# T06_preliminarySchematic_v3.net
KiCad netlist of a schematic drawn in EAGLE
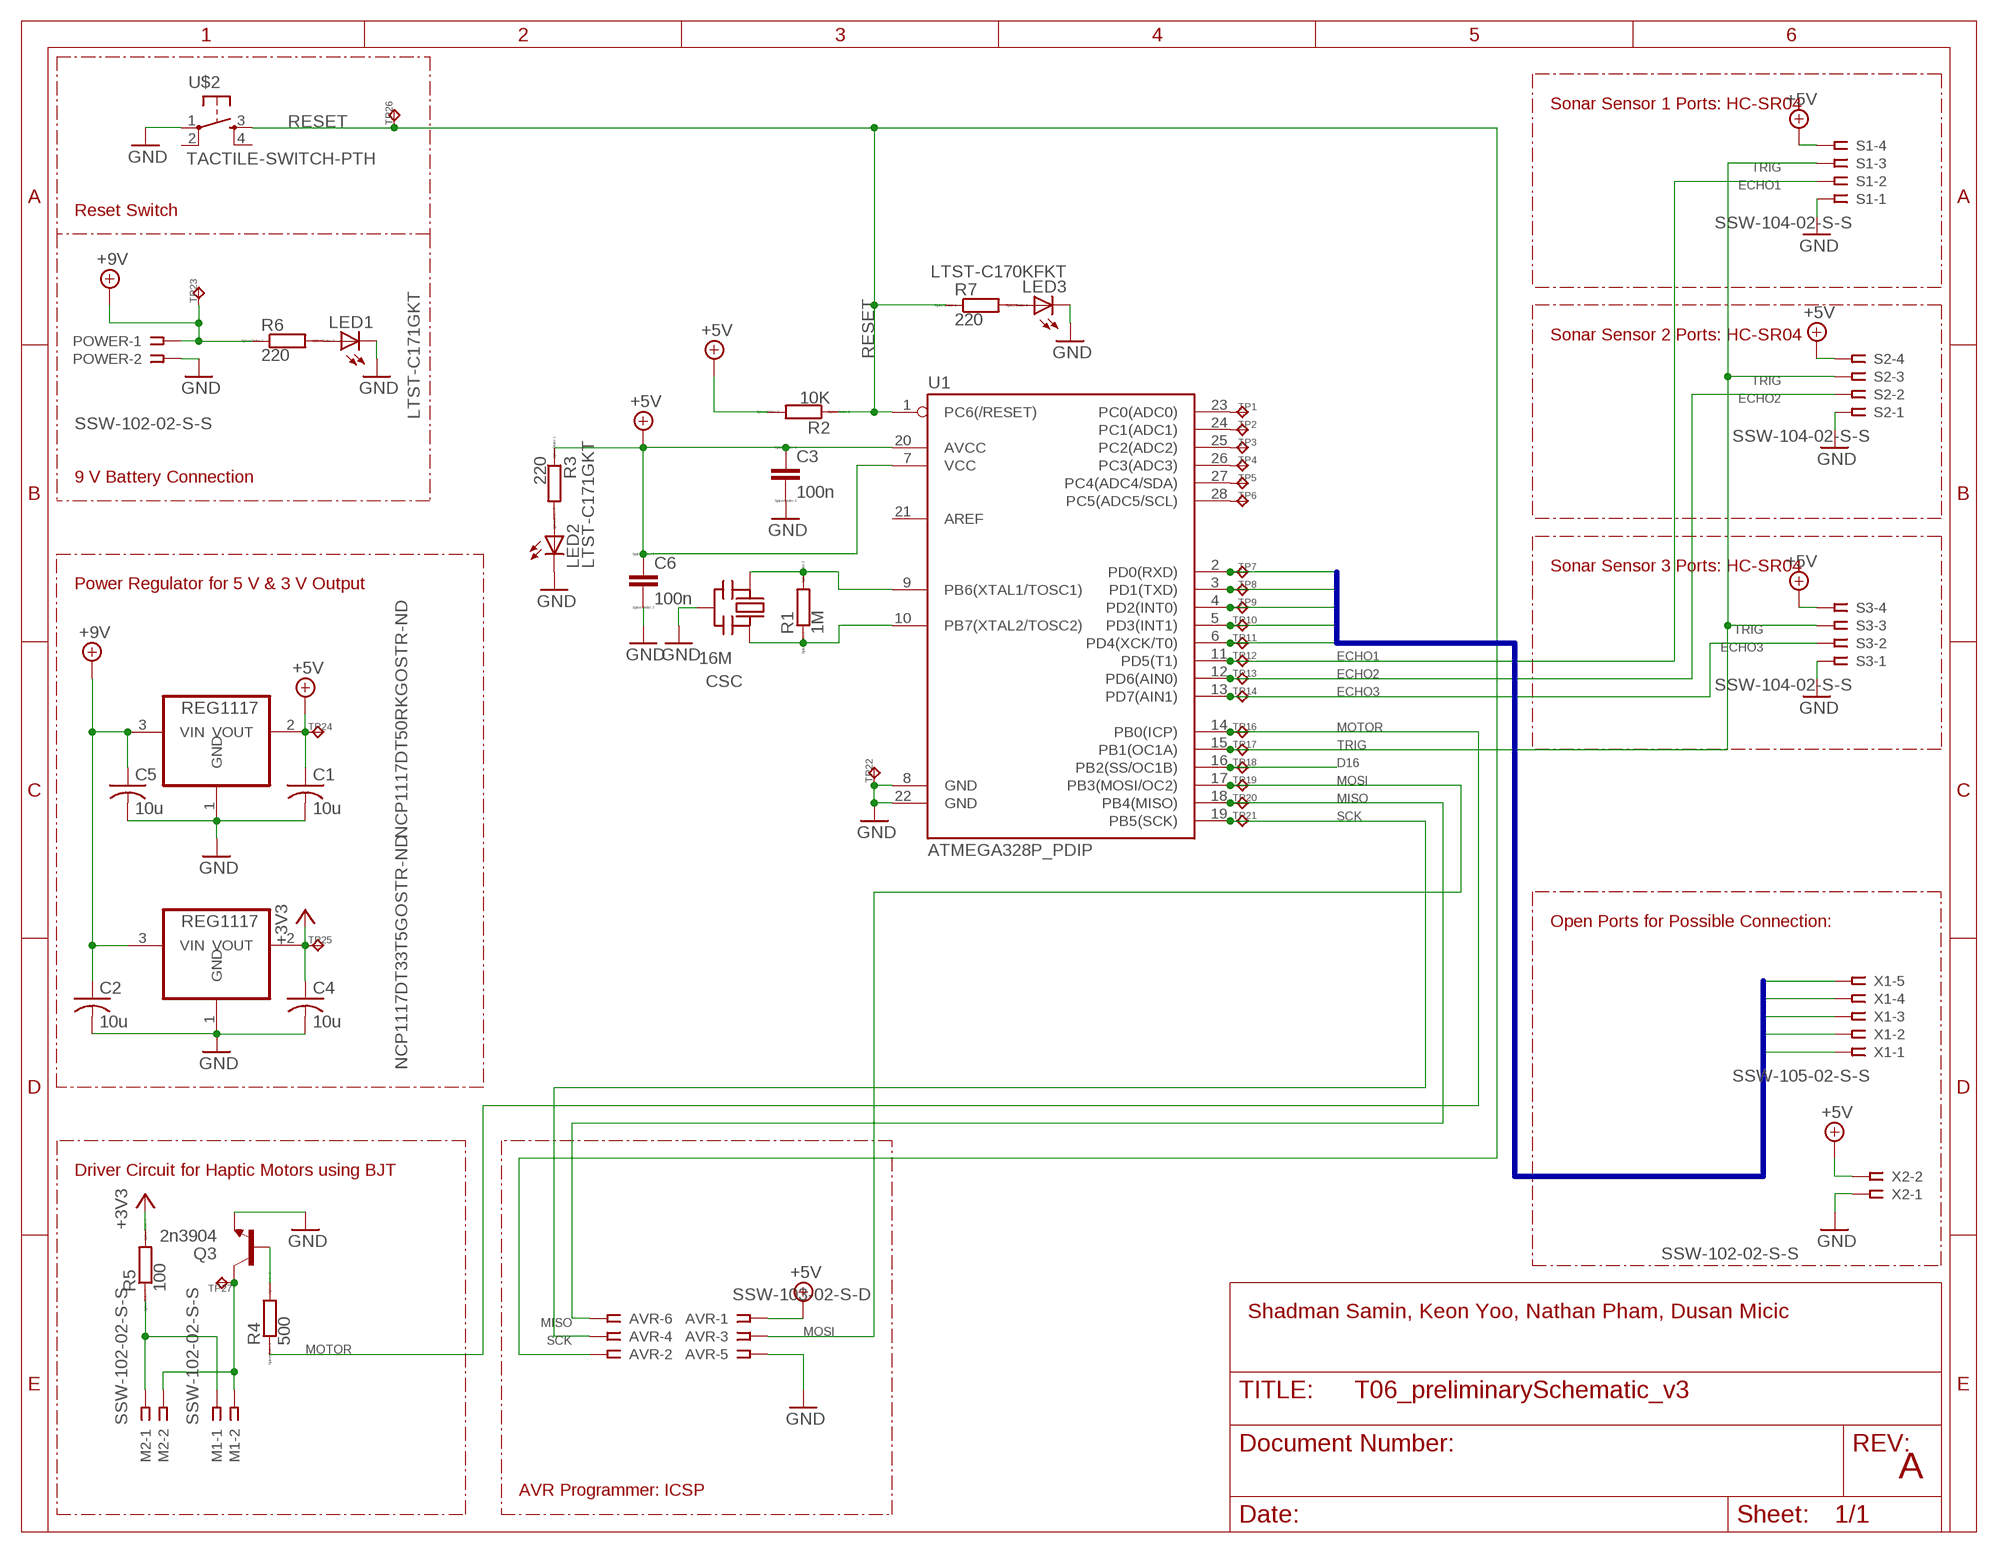
[diagram p0: schematic, sheet 1]

(export (version "E")
  (design (tool "Eeschema 10.0.6"))
  (components
    (comp (ref "AVR")
      (value "SSW-103-02-S-D")
      (footprint "eagle-import:SSW-103-02-S-D")
      (libsource (lib "eagle-import") (part "SSW-103-02-S-D"))
    )
    (comp (ref "C1")
      (value "10u")
      (footprint "eagle-import:C0805K")
      (libsource (lib "eagle-import") (part "C-USC0805K"))
    )
    (comp (ref "C2")
      (value "10u")
      (footprint "eagle-import:C0805K")
      (libsource (lib "eagle-import") (part "C-USC0805K"))
    )
    (comp (ref "C3")
      (value "100n")
      (footprint "eagle-import:C1005")
      (libsource (lib "eagle-import") (part "CC1005"))
    )
    (comp (ref "C4")
      (value "10u")
      (footprint "eagle-import:C0805K")
      (libsource (lib "eagle-import") (part "C-USC0805K"))
    )
    (comp (ref "C5")
      (value "10u")
      (footprint "eagle-import:C0805K")
      (libsource (lib "eagle-import") (part "C-USC0805K"))
    )
    (comp (ref "C6")
      (value "100n")
      (footprint "eagle-import:C1005")
      (libsource (lib "eagle-import") (part "CC1005"))
    )
    (comp (ref "CSC")
      (value "16M")
      (footprint "eagle-import:CSTCR-G")
      (libsource (lib "eagle-import") (part "CERMOSCILL-CSTCRG"))
    )
    (comp (ref "LED1")
      (value "LTST-C171GKT")
      (footprint "eagle-import:CHIPLED_0805")
      (libsource (lib "eagle-import") (part "LEDCHIPLED_0805"))
    )
    (comp (ref "LED2")
      (value "LTST-C171GKT")
      (footprint "eagle-import:CHIP-LED0805")
      (libsource (lib "eagle-import") (part "LEDCHIP-LED0805"))
    )
    (comp (ref "LED3")
      (value "LTST-C170KFKT")
      (footprint "eagle-import:CHIP-LED0805")
      (libsource (lib "eagle-import") (part "LEDCHIP-LED0805"))
    )
    (comp (ref "M1")
      (value "SSW-102-02-S-S")
      (footprint "eagle-import:SSW-102-02-S-S")
      (libsource (lib "eagle-import") (part "SSW-102-02-S-S"))
    )
    (comp (ref "M2")
      (value "SSW-102-02-S-S")
      (footprint "eagle-import:SSW-102-02-S-S")
      (libsource (lib "eagle-import") (part "SSW-102-02-S-S"))
    )
    (comp (ref "NCP1117DT33T5GOSTR-ND")
      (value "REG1117")
      (footprint "eagle-import:SOT223")
      (libsource (lib "eagle-import") (part "REG1117"))
    )
    (comp (ref "NCP1117DT50RKGOSTR-ND")
      (value "REG1117")
      (footprint "eagle-import:SOT223")
      (libsource (lib "eagle-import") (part "REG1117"))
    )
    (comp (ref "POWER")
      (value "SSW-102-02-S-S")
      (footprint "eagle-import:SSW-102-02-S-S")
      (libsource (lib "eagle-import") (part "SSW-102-02-S-S"))
    )
    (comp (ref "Q3")
      (value "2n3904")
      (footprint "eagle-import:TO-92")
      (libsource (lib "eagle-import") (part "TRANSISTOR_NPN2N3904"))
    )
    (comp (ref "R1")
      (value "1M")
      (footprint "eagle-import:R0603")
      (libsource (lib "eagle-import") (part "RR0603"))
    )
    (comp (ref "R2")
      (value "10K")
      (footprint "eagle-import:R0603")
      (libsource (lib "eagle-import") (part "RR0603"))
    )
    (comp (ref "R3")
      (value "220")
      (footprint "eagle-import:R0603")
      (libsource (lib "eagle-import") (part "RR0603"))
    )
    (comp (ref "R4")
      (value "500")
      (footprint "eagle-import:R0603")
      (libsource (lib "eagle-import") (part "RR0603"))
    )
    (comp (ref "R5")
      (value "100")
      (footprint "eagle-import:R0603")
      (libsource (lib "eagle-import") (part "RR0603"))
    )
    (comp (ref "R6")
      (value "220")
      (footprint "eagle-import:R0603")
      (libsource (lib "eagle-import") (part "RR0603"))
    )
    (comp (ref "R7")
      (value "220")
      (footprint "eagle-import:R0603")
      (libsource (lib "eagle-import") (part "RR0603"))
    )
    (comp (ref "S1")
      (value "SSW-104-02-S-S")
      (footprint "eagle-import:SSW-104-02-S-S")
      (libsource (lib "eagle-import") (part "SSW-104-02-S-S"))
    )
    (comp (ref "S2")
      (value "SSW-104-02-S-S")
      (footprint "eagle-import:SSW-104-02-S-S")
      (libsource (lib "eagle-import") (part "SSW-104-02-S-S"))
    )
    (comp (ref "S3")
      (value "SSW-104-02-S-S")
      (footprint "eagle-import:SSW-104-02-S-S")
      (libsource (lib "eagle-import") (part "SSW-104-02-S-S"))
    )
    (comp (ref "TP1")
      (value "TPPAD1-13")
      (footprint "eagle-import:P1-13")
      (libsource (lib "eagle-import") (part "TPPAD1-13"))
    )
    (comp (ref "TP2")
      (value "TPPAD1-13")
      (footprint "eagle-import:P1-13")
      (libsource (lib "eagle-import") (part "TPPAD1-13"))
    )
    (comp (ref "TP3")
      (value "TPPAD1-13")
      (footprint "eagle-import:P1-13")
      (libsource (lib "eagle-import") (part "TPPAD1-13"))
    )
    (comp (ref "TP4")
      (value "TPPAD1-13")
      (footprint "eagle-import:P1-13")
      (libsource (lib "eagle-import") (part "TPPAD1-13"))
    )
    (comp (ref "TP5")
      (value "TPPAD1-13")
      (footprint "eagle-import:P1-13")
      (libsource (lib "eagle-import") (part "TPPAD1-13"))
    )
    (comp (ref "TP6")
      (value "TPPAD1-13")
      (footprint "eagle-import:P1-13")
      (libsource (lib "eagle-import") (part "TPPAD1-13"))
    )
    (comp (ref "TP7")
      (value "TPPAD1-13")
      (footprint "eagle-import:P1-13")
      (libsource (lib "eagle-import") (part "TPPAD1-13"))
    )
    (comp (ref "TP8")
      (value "TPPAD1-13")
      (footprint "eagle-import:P1-13")
      (libsource (lib "eagle-import") (part "TPPAD1-13"))
    )
    (comp (ref "TP9")
      (value "TPPAD1-13")
      (footprint "eagle-import:P1-13")
      (libsource (lib "eagle-import") (part "TPPAD1-13"))
    )
    (comp (ref "TP10")
      (value "TPPAD1-13")
      (footprint "eagle-import:P1-13")
      (libsource (lib "eagle-import") (part "TPPAD1-13"))
    )
    (comp (ref "TP11")
      (value "TPPAD1-13")
      (footprint "eagle-import:P1-13")
      (libsource (lib "eagle-import") (part "TPPAD1-13"))
    )
    (comp (ref "TP12")
      (value "TPPAD1-13")
      (footprint "eagle-import:P1-13")
      (libsource (lib "eagle-import") (part "TPPAD1-13"))
    )
    (comp (ref "TP13")
      (value "TPPAD1-13")
      (footprint "eagle-import:P1-13")
      (libsource (lib "eagle-import") (part "TPPAD1-13"))
    )
    (comp (ref "TP14")
      (value "TPPAD1-13")
      (footprint "eagle-import:P1-13")
      (libsource (lib "eagle-import") (part "TPPAD1-13"))
    )
    (comp (ref "TP16")
      (value "TPPAD1-13")
      (footprint "eagle-import:P1-13")
      (libsource (lib "eagle-import") (part "TPPAD1-13"))
    )
    (comp (ref "TP17")
      (value "TPPAD1-13")
      (footprint "eagle-import:P1-13")
      (libsource (lib "eagle-import") (part "TPPAD1-13"))
    )
    (comp (ref "TP18")
      (value "TPPAD1-13")
      (footprint "eagle-import:P1-13")
      (libsource (lib "eagle-import") (part "TPPAD1-13"))
    )
    (comp (ref "TP19")
      (value "TPPAD1-13")
      (footprint "eagle-import:P1-13")
      (libsource (lib "eagle-import") (part "TPPAD1-13"))
    )
    (comp (ref "TP20")
      (value "TPPAD1-13")
      (footprint "eagle-import:P1-13")
      (libsource (lib "eagle-import") (part "TPPAD1-13"))
    )
    (comp (ref "TP21")
      (value "TPPAD1-13")
      (footprint "eagle-import:P1-13")
      (libsource (lib "eagle-import") (part "TPPAD1-13"))
    )
    (comp (ref "TP22")
      (value "TPPAD1-13")
      (footprint "eagle-import:P1-13")
      (libsource (lib "eagle-import") (part "TPPAD1-13"))
    )
    (comp (ref "TP23")
      (value "TPPAD1-13")
      (footprint "eagle-import:P1-13")
      (libsource (lib "eagle-import") (part "TPPAD1-13"))
    )
    (comp (ref "TP24")
      (value "TPPAD1-13")
      (footprint "eagle-import:P1-13")
      (libsource (lib "eagle-import") (part "TPPAD1-13"))
    )
    (comp (ref "TP25")
      (value "TPPAD1-13")
      (footprint "eagle-import:P1-13")
      (libsource (lib "eagle-import") (part "TPPAD1-13"))
    )
    (comp (ref "TP26")
      (value "TPPAD1-13")
      (footprint "eagle-import:P1-13")
      (libsource (lib "eagle-import") (part "TPPAD1-13"))
    )
    (comp (ref "TP27")
      (value "TPPAD1-13")
      (footprint "eagle-import:P1-13")
      (libsource (lib "eagle-import") (part "TPPAD1-13"))
    )
    (comp (ref "U$2")
      (value "TACTILE-SWITCH-PTH")
      (footprint "eagle-import:TAC-SWITCH-PTH")
      (libsource (lib "eagle-import") (part "TACTILE-SWITCH-PTH"))
    )
    (comp (ref "U1")
      (value "ATMEGA328P_PDIP")
      (footprint "eagle-import:DIL28-3")
      (libsource (lib "eagle-import") (part "ATMEGA328P_PDIP"))
    )
    (comp (ref "X1")
      (value "SSW-105-02-S-S")
      (footprint "eagle-import:SSW-105-02-S-S")
      (libsource (lib "eagle-import") (part "SSW-105-02-S-S"))
    )
    (comp (ref "X2")
      (value "SSW-102-02-S-S")
      (footprint "eagle-import:SSW-102-02-S-S")
      (libsource (lib "eagle-import") (part "SSW-102-02-S-S"))
    )
  )
  (nets
    (net (code "1") (name "+3V3") (class "Default")
      (node (ref "C4") (pin "1") (pinfunction "1_1") (pintype "passive"))
      (node (ref "NCP1117DT33T5GOSTR-ND") (pin "2") (pinfunction "VOUT_2") (pintype "output"))
      (node (ref "R5") (pin "2") (pinfunction "2_2") (pintype "passive"))
      (node (ref "TP25") (pin "TP") (pinfunction "TP_TP") (pintype "input"))
    )
    (net (code "2") (name "+5V") (class "Default")
      (node (ref "AVR") (pin "1") (pinfunction "1_1") (pintype "passive"))
      (node (ref "C1") (pin "1") (pinfunction "1_1") (pintype "passive"))
      (node (ref "C3") (pin "1") (pinfunction "1_1") (pintype "passive"))
      (node (ref "C6") (pin "1") (pinfunction "1_1") (pintype "passive"))
      (node (ref "NCP1117DT50RKGOSTR-ND") (pin "2") (pinfunction "VOUT_2") (pintype "output"))
      (node (ref "R2") (pin "2") (pinfunction "2_2") (pintype "passive"))
      (node (ref "R3") (pin "1") (pinfunction "1_1") (pintype "passive"))
      (node (ref "S1") (pin "4") (pinfunction "1_4") (pintype "passive"))
      (node (ref "S2") (pin "4") (pinfunction "1_4") (pintype "passive"))
      (node (ref "S3") (pin "4") (pinfunction "1_4") (pintype "passive"))
      (node (ref "TP24") (pin "TP") (pinfunction "TP_TP") (pintype "input"))
      (node (ref "U1") (pin "20") (pinfunction "AVCC_20") (pintype "bidirectional"))
      (node (ref "U1") (pin "7") (pinfunction "VCC_7") (pintype "bidirectional"))
      (node (ref "X2") (pin "2") (pinfunction "1_2") (pintype "passive"))
    )
    (net (code "3") (name "+9V") (class "Default")
      (node (ref "C2") (pin "1") (pinfunction "1_1") (pintype "passive"))
      (node (ref "C5") (pin "1") (pinfunction "1_1") (pintype "passive"))
      (node (ref "NCP1117DT33T5GOSTR-ND") (pin "3") (pinfunction "VIN_3") (pintype "input"))
      (node (ref "NCP1117DT50RKGOSTR-ND") (pin "3") (pinfunction "VIN_3") (pintype "input"))
      (node (ref "POWER") (pin "1") (pinfunction "1_1") (pintype "passive"))
      (node (ref "R6") (pin "1") (pinfunction "1_1") (pintype "passive"))
      (node (ref "TP23") (pin "TP") (pinfunction "TP_TP") (pintype "input"))
    )
    (net (code "4") (name "/BU0") (class "Default")
      (node (ref "TP7") (pin "TP") (pinfunction "TP_TP") (pintype "input"))
      (node (ref "U1") (pin "2") (pinfunction "PD0(RXD)_2") (pintype "bidirectional"))
      (node (ref "X1") (pin "1") (pinfunction "1_1") (pintype "passive"))
    )
    (net (code "5") (name "/BU1") (class "Default")
      (node (ref "TP8") (pin "TP") (pinfunction "TP_TP") (pintype "input"))
      (node (ref "U1") (pin "3") (pinfunction "PD1(TXD)_3") (pintype "bidirectional"))
      (node (ref "X1") (pin "2") (pinfunction "1_2") (pintype "passive"))
    )
    (net (code "6") (name "/BU2") (class "Default")
      (node (ref "TP9") (pin "TP") (pinfunction "TP_TP") (pintype "input"))
      (node (ref "U1") (pin "4") (pinfunction "PD2(INT0)_4") (pintype "bidirectional"))
      (node (ref "X1") (pin "3") (pinfunction "1_3") (pintype "passive"))
    )
    (net (code "7") (name "/BU3") (class "Default")
      (node (ref "TP10") (pin "TP") (pinfunction "TP_TP") (pintype "input"))
      (node (ref "U1") (pin "5") (pinfunction "PD3(INT1)_5") (pintype "bidirectional"))
      (node (ref "X1") (pin "4") (pinfunction "1_4") (pintype "passive"))
    )
    (net (code "8") (name "/BU4") (class "Default")
      (node (ref "TP11") (pin "TP") (pinfunction "TP_TP") (pintype "input"))
      (node (ref "U1") (pin "6") (pinfunction "PD4(XCK/T0)_6") (pintype "bidirectional"))
      (node (ref "X1") (pin "5") (pinfunction "1_5") (pintype "passive"))
    )
    (net (code "9") (name "/D16") (class "Default")
      (node (ref "TP18") (pin "TP") (pinfunction "TP_TP") (pintype "input"))
      (node (ref "U1") (pin "16") (pinfunction "PB2(SS/OC1B)_16") (pintype "bidirectional"))
    )
    (net (code "10") (name "/ECHO1") (class "Default")
      (node (ref "S1") (pin "2") (pinfunction "1_2") (pintype "passive"))
      (node (ref "TP12") (pin "TP") (pinfunction "TP_TP") (pintype "input"))
      (node (ref "U1") (pin "11") (pinfunction "PD5(T1)_11") (pintype "bidirectional"))
    )
    (net (code "11") (name "/ECHO2") (class "Default")
      (node (ref "S2") (pin "2") (pinfunction "1_2") (pintype "passive"))
      (node (ref "TP13") (pin "TP") (pinfunction "TP_TP") (pintype "input"))
      (node (ref "U1") (pin "12") (pinfunction "PD6(AIN0)_12") (pintype "bidirectional"))
    )
    (net (code "12") (name "/ECHO3") (class "Default")
      (node (ref "S3") (pin "2") (pinfunction "1_2") (pintype "passive"))
      (node (ref "TP14") (pin "TP") (pinfunction "TP_TP") (pintype "input"))
      (node (ref "U1") (pin "13") (pinfunction "PD7(AIN1)_13") (pintype "bidirectional"))
    )
    (net (code "13") (name "/MISO") (class "Default")
      (node (ref "AVR") (pin "6") (pinfunction "1_6") (pintype "passive"))
      (node (ref "TP20") (pin "TP") (pinfunction "TP_TP") (pintype "input"))
      (node (ref "U1") (pin "18") (pinfunction "PB4(MISO)_18") (pintype "bidirectional"))
    )
    (net (code "14") (name "/MOSI") (class "Default")
      (node (ref "AVR") (pin "3") (pinfunction "1_3") (pintype "passive"))
      (node (ref "TP19") (pin "TP") (pinfunction "TP_TP") (pintype "input"))
      (node (ref "U1") (pin "17") (pinfunction "PB3(MOSI/OC2)_17") (pintype "bidirectional"))
    )
    (net (code "15") (name "/MOTOR") (class "Default")
      (node (ref "R4") (pin "1") (pinfunction "1_1") (pintype "passive"))
      (node (ref "TP16") (pin "TP") (pinfunction "TP_TP") (pintype "input"))
      (node (ref "U1") (pin "14") (pinfunction "PB0(ICP)_14") (pintype "bidirectional"))
    )
    (net (code "16") (name "/RESET") (class "Default")
      (node (ref "AVR") (pin "2") (pinfunction "1_2") (pintype "passive"))
      (node (ref "R2") (pin "1") (pinfunction "1_1") (pintype "passive"))
      (node (ref "R7") (pin "1") (pinfunction "1_1") (pintype "passive"))
      (node (ref "TP26") (pin "TP") (pinfunction "TP_TP") (pintype "input"))
      (node (ref "U$2") (pin "3") (pinfunction "3_3") (pintype "passive"))
      (node (ref "U1") (pin "1") (pinfunction "PC6(/RESET)_1") (pintype "bidirectional"))
    )
    (net (code "17") (name "/SCK") (class "Default")
      (node (ref "AVR") (pin "4") (pinfunction "1_4") (pintype "passive"))
      (node (ref "TP21") (pin "TP") (pinfunction "TP_TP") (pintype "input"))
      (node (ref "U1") (pin "19") (pinfunction "PB5(SCK)_19") (pintype "bidirectional"))
    )
    (net (code "18") (name "/TRIG") (class "Default")
      (node (ref "S1") (pin "3") (pinfunction "1_3") (pintype "passive"))
      (node (ref "S2") (pin "3") (pinfunction "1_3") (pintype "passive"))
      (node (ref "S3") (pin "3") (pinfunction "1_3") (pintype "passive"))
      (node (ref "TP17") (pin "TP") (pinfunction "TP_TP") (pintype "input"))
      (node (ref "U1") (pin "15") (pinfunction "PB1(OC1A)_15") (pintype "bidirectional"))
    )
    (net (code "19") (name "GND") (class "Default")
      (node (ref "AVR") (pin "5") (pinfunction "1_5") (pintype "passive"))
      (node (ref "C1") (pin "2") (pinfunction "2_2") (pintype "passive"))
      (node (ref "C2") (pin "2") (pinfunction "2_2") (pintype "passive"))
      (node (ref "C3") (pin "2") (pinfunction "2_2") (pintype "passive"))
      (node (ref "C4") (pin "2") (pinfunction "2_2") (pintype "passive"))
      (node (ref "C5") (pin "2") (pinfunction "2_2") (pintype "passive"))
      (node (ref "C6") (pin "2") (pinfunction "2_2") (pintype "passive"))
      (node (ref "CSC") (pin "2") (pinfunction "GND_2") (pintype "bidirectional"))
      (node (ref "LED1") (pin "C") (pinfunction "C_C") (pintype "passive"))
      (node (ref "LED2") (pin "C") (pinfunction "C_C") (pintype "passive"))
      (node (ref "LED3") (pin "C") (pinfunction "C_C") (pintype "passive"))
      (node (ref "NCP1117DT33T5GOSTR-ND") (pin "1") (pinfunction "GND_1") (pintype "power_in"))
      (node (ref "NCP1117DT50RKGOSTR-ND") (pin "1") (pinfunction "GND_1") (pintype "power_in"))
      (node (ref "POWER") (pin "2") (pinfunction "1_2") (pintype "passive"))
      (node (ref "Q3") (pin "1") (pinfunction "E_1") (pintype "passive"))
      (node (ref "S1") (pin "1") (pinfunction "1_1") (pintype "passive"))
      (node (ref "S2") (pin "1") (pinfunction "1_1") (pintype "passive"))
      (node (ref "S3") (pin "1") (pinfunction "1_1") (pintype "passive"))
      (node (ref "TP22") (pin "TP") (pinfunction "TP_TP") (pintype "input"))
      (node (ref "U$2") (pin "1") (pinfunction "1_1") (pintype "passive"))
      (node (ref "U1") (pin "22") (pinfunction "GND_22") (pintype "bidirectional"))
      (node (ref "U1") (pin "8") (pinfunction "GND_8") (pintype "bidirectional"))
      (node (ref "X2") (pin "1") (pinfunction "1_1") (pintype "passive"))
    )
    (net (code "20") (name "Net-(CSC-IN)") (class "Default")
      (node (ref "CSC") (pin "1") (pinfunction "IN_1") (pintype "bidirectional"))
      (node (ref "R1") (pin "2") (pinfunction "2_2") (pintype "passive"))
      (node (ref "U1") (pin "9") (pinfunction "PB6(XTAL1/TOSC1)_9") (pintype "bidirectional"))
    )
    (net (code "21") (name "Net-(CSC-OUT)") (class "Default")
      (node (ref "CSC") (pin "3") (pinfunction "OUT_3") (pintype "bidirectional"))
      (node (ref "R1") (pin "1") (pinfunction "1_1") (pintype "passive"))
      (node (ref "U1") (pin "10") (pinfunction "PB7(XTAL2/TOSC2)_10") (pintype "bidirectional"))
    )
    (net (code "22") (name "Net-(LED1-PadA)") (class "Default")
      (node (ref "LED1") (pin "A") (pinfunction "A_A") (pintype "passive"))
      (node (ref "R6") (pin "2") (pinfunction "2_2") (pintype "passive"))
    )
    (net (code "23") (name "Net-(LED2-PadA)") (class "Default")
      (node (ref "LED2") (pin "A") (pinfunction "A_A") (pintype "passive"))
      (node (ref "R3") (pin "2") (pinfunction "2_2") (pintype "passive"))
    )
    (net (code "24") (name "Net-(LED3-PadA)") (class "Default")
      (node (ref "LED3") (pin "A") (pinfunction "A_A") (pintype "passive"))
      (node (ref "R7") (pin "2") (pinfunction "2_2") (pintype "passive"))
    )
    (net (code "25") (name "Net-(M1-Pad1)") (class "Default")
      (node (ref "M1") (pin "1") (pinfunction "1_1") (pintype "passive"))
      (node (ref "M2") (pin "1") (pinfunction "1_1") (pintype "passive"))
      (node (ref "R5") (pin "1") (pinfunction "1_1") (pintype "passive"))
    )
    (net (code "26") (name "Net-(M1B-1)") (class "Default")
      (node (ref "M1") (pin "2") (pinfunction "1_2") (pintype "passive"))
      (node (ref "M2") (pin "2") (pinfunction "1_2") (pintype "passive"))
      (node (ref "Q3") (pin "3") (pinfunction "C_3") (pintype "passive"))
      (node (ref "TP27") (pin "TP") (pinfunction "TP_TP") (pintype "input"))
    )
    (net (code "27") (name "Net-(Q3-B)") (class "Default")
      (node (ref "Q3") (pin "2") (pinfunction "B_2") (pintype "passive"))
      (node (ref "R4") (pin "2") (pinfunction "2_2") (pintype "passive"))
    )
    (net (code "28") (name "Net-(U1-PC0(ADC0))") (class "Default")
      (node (ref "TP1") (pin "TP") (pinfunction "TP_TP") (pintype "input"))
      (node (ref "U1") (pin "23") (pinfunction "PC0(ADC0)_23") (pintype "bidirectional"))
    )
    (net (code "29") (name "Net-(U1-PC1(ADC1))") (class "Default")
      (node (ref "TP2") (pin "TP") (pinfunction "TP_TP") (pintype "input"))
      (node (ref "U1") (pin "24") (pinfunction "PC1(ADC1)_24") (pintype "bidirectional"))
    )
    (net (code "30") (name "Net-(U1-PC2(ADC2))") (class "Default")
      (node (ref "TP3") (pin "TP") (pinfunction "TP_TP") (pintype "input"))
      (node (ref "U1") (pin "25") (pinfunction "PC2(ADC2)_25") (pintype "bidirectional"))
    )
    (net (code "31") (name "Net-(U1-PC3(ADC3))") (class "Default")
      (node (ref "TP4") (pin "TP") (pinfunction "TP_TP") (pintype "input"))
      (node (ref "U1") (pin "26") (pinfunction "PC3(ADC3)_26") (pintype "bidirectional"))
    )
    (net (code "32") (name "Net-(U1-PC4(ADC4{slash}SDA))") (class "Default")
      (node (ref "TP5") (pin "TP") (pinfunction "TP_TP") (pintype "input"))
      (node (ref "U1") (pin "27") (pinfunction "PC4(ADC4/SDA)_27") (pintype "bidirectional"))
    )
    (net (code "33") (name "Net-(U1-PC5(ADC5{slash}SCL))") (class "Default")
      (node (ref "TP6") (pin "TP") (pinfunction "TP_TP") (pintype "input"))
      (node (ref "U1") (pin "28") (pinfunction "PC5(ADC5/SCL)_28") (pintype "bidirectional"))
    )
    (net (code "34") (name "unconnected-(U$2-Pad2)") (class "Default")
      (node (ref "U$2") (pin "2") (pinfunction "2_2") (pintype "passive"))
    )
    (net (code "35") (name "unconnected-(U$2-Pad4)") (class "Default")
      (node (ref "U$2") (pin "4") (pinfunction "4_4") (pintype "passive"))
    )
    (net (code "36") (name "unconnected-(U1-AREF-Pad21)") (class "Default")
      (node (ref "U1") (pin "21") (pinfunction "AREF_21") (pintype "bidirectional"))
    )
  )
)
